# Schematics.net
KiCad netlist of a schematic drawn in Altium Designer
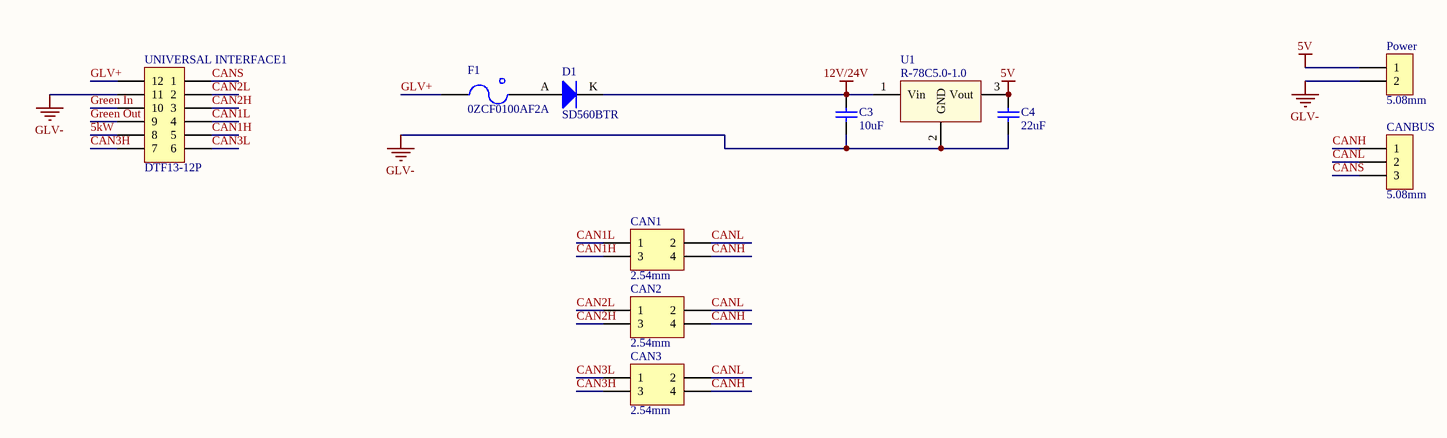
[diagram p0: Schematics.SchDoc]

(export (version "E")
  (design (tool "Eeschema 10.0.6"))
  (components
    (comp (ref "C3")
      (value "10uF")
      (footprint "0805")
      (fields
        (field (name "PART NUMBER") "GRM21BR6YA106KE43L")
        (field (name "TOLERANCE") "10%")
        (field (name "MANUFACTURER") "muRata")
      )
      (libsource (lib "ts_20-standard-library") (part "Capacitor"))
    )
    (comp (ref "C4")
      (value "22uF")
      (footprint "1206")
      (fields
        (field (name "PART NUMBER") "CC1206MKX5R7BB226")
        (field (name "TOLERANCE") "20%")
        (field (name "MANUFACTURER") "YAGEO")
      )
      (libsource (lib "ts_20-standard-library") (part "Capacitor"))
    )
    (comp (ref "CAN1")
      (value "2.54mm")
      (footprint "TH 2.54mm Header 2x2")
      (fields (field (name "PART NUMBER") "TH 2.54mm Header 2x2") (field (name "CONTACT") "NA"))
      (libsource (lib "ts_20-standard-connectors") (part "Header 2x2"))
    )
    (comp (ref "CAN2")
      (value "2.54mm")
      (footprint "TH 2.54mm Header 2x2")
      (fields (field (name "PART NUMBER") "TH 2.54mm Header 2x2") (field (name "CONTACT") "NA"))
      (libsource (lib "ts_20-standard-connectors") (part "Header 2x2"))
    )
    (comp (ref "CAN3")
      (value "2.54mm")
      (footprint "TH 2.54mm Header 2x2")
      (fields (field (name "PART NUMBER") "TH 2.54mm Header 2x2") (field (name "CONTACT") "NA"))
      (libsource (lib "ts_20-standard-connectors") (part "Header 2x2"))
    )
    (comp (ref "CANBUS")
      (value "5.08mm")
      (footprint "TH 5.08mm Header 1x3")
      (fields
        (field (name "PART NUMBER") "1760520000")
        (field (name "DIGIKEY PART NUMBER") "281-1883-ND")
        (field (name "CONTACT") "NA")
      )
      (libsource (lib "ts_20-standard-connectors") (part "Header 1x3"))
    )
    (comp (ref "D1")
      (value "SD560BTR")
      (footprint "SMB Diode")
      (description "1.2V_F 600V 5A SMB")
      (fields
        (field (name "MANUFACTURER") "SMC Diode Solutions")
        (field (name "DIGIKEY PART NUMBER") "1655-1530-2-ND")
      )
      (libsource (lib "ts_20-standard-library") (part "Diode"))
    )
    (comp (ref "F1")
      (value "0ZCF0100AF2A")
      (footprint "2920")
      (description "PTC RESET FUSE 60V 1A 292")
      (fields
        (field (name "MANUFACTURER") "Littelfuse Inc.")
        (field (name "DIGIKEY PART NUMBER") "507-2070-1-ND")
      )
      (libsource (lib "ts_20-standard-library") (part "PTC Fuse"))
    )
    (comp (ref "Power")
      (value "5.08mm")
      (footprint "TH 5.08mm Header 1x2")
      (fields
        (field (name "PART NUMBER") "1760510000")
        (field (name "DIGIKEY PART NUMBER") "281-1882-ND")
        (field (name "CONTACT") "NA")
      )
      (libsource (lib "ts_20-standard-connectors") (part "Header 1x2"))
    )
    (comp (ref "U1")
      (value "R-78C5.0-1.0")
      (footprint "RECOM 3-SIP")
      (description "CONV DC/DC 1A 5V OUT SIP VERT")
      (fields (field (name "MANUFACTURER") "Recom") (field (name "DIGIKEY PART NUMBER") "945-1395-5-ND"))
      (libsource (lib "ts_20-standard-library") (part "R-78C5.0-1.0"))
    )
    (comp (ref "UNIVERSAL INTERFACE1")
      (value "DTF13-12P")
      (footprint "DTF13-12P")
      (fields (field (name "DIGIKEY PART NUMBER") "1734-1861-ND") (field (name "CONTACT") "Copper Alloy"))
      (libsource (lib "ts_20-standard-connectors") (part "DT13-12P"))
    )
  )
  (nets
    (net (code "1") (name "/5kW") (class "Default")
      (node (ref "UNIVERSAL INTERFACE1") (pin "8") (pinfunction "8_8") (pintype "passive"))
    )
    (net (code "2") (name "/CAN1H") (class "Default")
      (node (ref "CAN1") (pin "3") (pinfunction "3_3") (pintype "passive"))
      (node (ref "UNIVERSAL INTERFACE1") (pin "5") (pinfunction "5_5") (pintype "power_in"))
    )
    (net (code "3") (name "/CAN1L") (class "Default")
      (node (ref "CAN1") (pin "1") (pinfunction "1_1") (pintype "passive"))
      (node (ref "UNIVERSAL INTERFACE1") (pin "4") (pinfunction "4_4") (pintype "power_in"))
    )
    (net (code "4") (name "/CAN2H") (class "Default")
      (node (ref "CAN2") (pin "3") (pinfunction "3_3") (pintype "passive"))
      (node (ref "UNIVERSAL INTERFACE1") (pin "3") (pinfunction "3_3") (pintype "power_in"))
    )
    (net (code "5") (name "/CAN2L") (class "Default")
      (node (ref "CAN2") (pin "1") (pinfunction "1_1") (pintype "passive"))
      (node (ref "UNIVERSAL INTERFACE1") (pin "2") (pinfunction "2_2") (pintype "power_in"))
    )
    (net (code "6") (name "/CAN3H") (class "Default")
      (node (ref "CAN3") (pin "3") (pinfunction "3_3") (pintype "passive"))
      (node (ref "UNIVERSAL INTERFACE1") (pin "7") (pinfunction "7_7") (pintype "passive"))
    )
    (net (code "7") (name "/CAN3L") (class "Default")
      (node (ref "CAN3") (pin "1") (pinfunction "1_1") (pintype "passive"))
      (node (ref "UNIVERSAL INTERFACE1") (pin "6") (pinfunction "6_6") (pintype "power_in"))
    )
    (net (code "8") (name "/CANH") (class "Default")
      (node (ref "CAN1") (pin "4") (pinfunction "4_4") (pintype "passive"))
      (node (ref "CAN2") (pin "4") (pinfunction "4_4") (pintype "passive"))
      (node (ref "CAN3") (pin "4") (pinfunction "4_4") (pintype "passive"))
      (node (ref "CANBUS") (pin "1") (pinfunction "1_1") (pintype "passive"))
    )
    (net (code "9") (name "/CANL") (class "Default")
      (node (ref "CAN1") (pin "2") (pinfunction "2_2") (pintype "passive"))
      (node (ref "CAN2") (pin "2") (pinfunction "2_2") (pintype "passive"))
      (node (ref "CAN3") (pin "2") (pinfunction "2_2") (pintype "passive"))
      (node (ref "CANBUS") (pin "2") (pinfunction "2_2") (pintype "passive"))
    )
    (net (code "10") (name "/CANS") (class "Default")
      (node (ref "CANBUS") (pin "3") (pinfunction "3_3") (pintype "passive"))
      (node (ref "UNIVERSAL INTERFACE1") (pin "1") (pinfunction "1_1") (pintype "power_in"))
    )
    (net (code "11") (name "/GLV+") (class "Default")
      (node (ref "F1") (pin "1") (pinfunction "1_1") (pintype "passive"))
      (node (ref "UNIVERSAL INTERFACE1") (pin "12") (pinfunction "12_12") (pintype "passive"))
    )
    (net (code "12") (name "/Green In") (class "Default")
      (node (ref "UNIVERSAL INTERFACE1") (pin "10") (pinfunction "10_10") (pintype "passive"))
    )
    (net (code "13") (name "/Green Out") (class "Default")
      (node (ref "UNIVERSAL INTERFACE1") (pin "9") (pinfunction "9_9") (pintype "passive"))
    )
    (net (code "14") (name "5V") (class "Default")
      (node (ref "C4") (pin "2") (pinfunction "2_2") (pintype "passive"))
      (node (ref "Power") (pin "1") (pinfunction "1_1") (pintype "passive"))
      (node (ref "U1") (pin "3") (pinfunction "Vout_3") (pintype "passive"))
    )
    (net (code "15") (name "12V{slash}24V") (class "Default")
      (node (ref "C3") (pin "2") (pinfunction "2_2") (pintype "passive"))
      (node (ref "D1") (pin "K") (pinfunction "K_K") (pintype "passive"))
      (node (ref "U1") (pin "1") (pinfunction "Vin_1") (pintype "passive"))
    )
    (net (code "16") (name "GLV-") (class "Default")
      (node (ref "C3") (pin "1") (pinfunction "1_1") (pintype "passive"))
      (node (ref "C4") (pin "1") (pinfunction "1_1") (pintype "passive"))
      (node (ref "Power") (pin "2") (pinfunction "2_2") (pintype "passive"))
      (node (ref "U1") (pin "2") (pinfunction "GND_2") (pintype "passive"))
      (node (ref "UNIVERSAL INTERFACE1") (pin "11") (pinfunction "11_11") (pintype "passive"))
    )
    (net (code "17") (name "Net-(D1-PadA)") (class "Default")
      (node (ref "D1") (pin "A") (pinfunction "A_A") (pintype "passive"))
      (node (ref "F1") (pin "2") (pinfunction "2_2") (pintype "passive"))
    )
  )
)
